# C-08_eMMC.net
KiCad netlist of a schematic drawn in Altium Designer
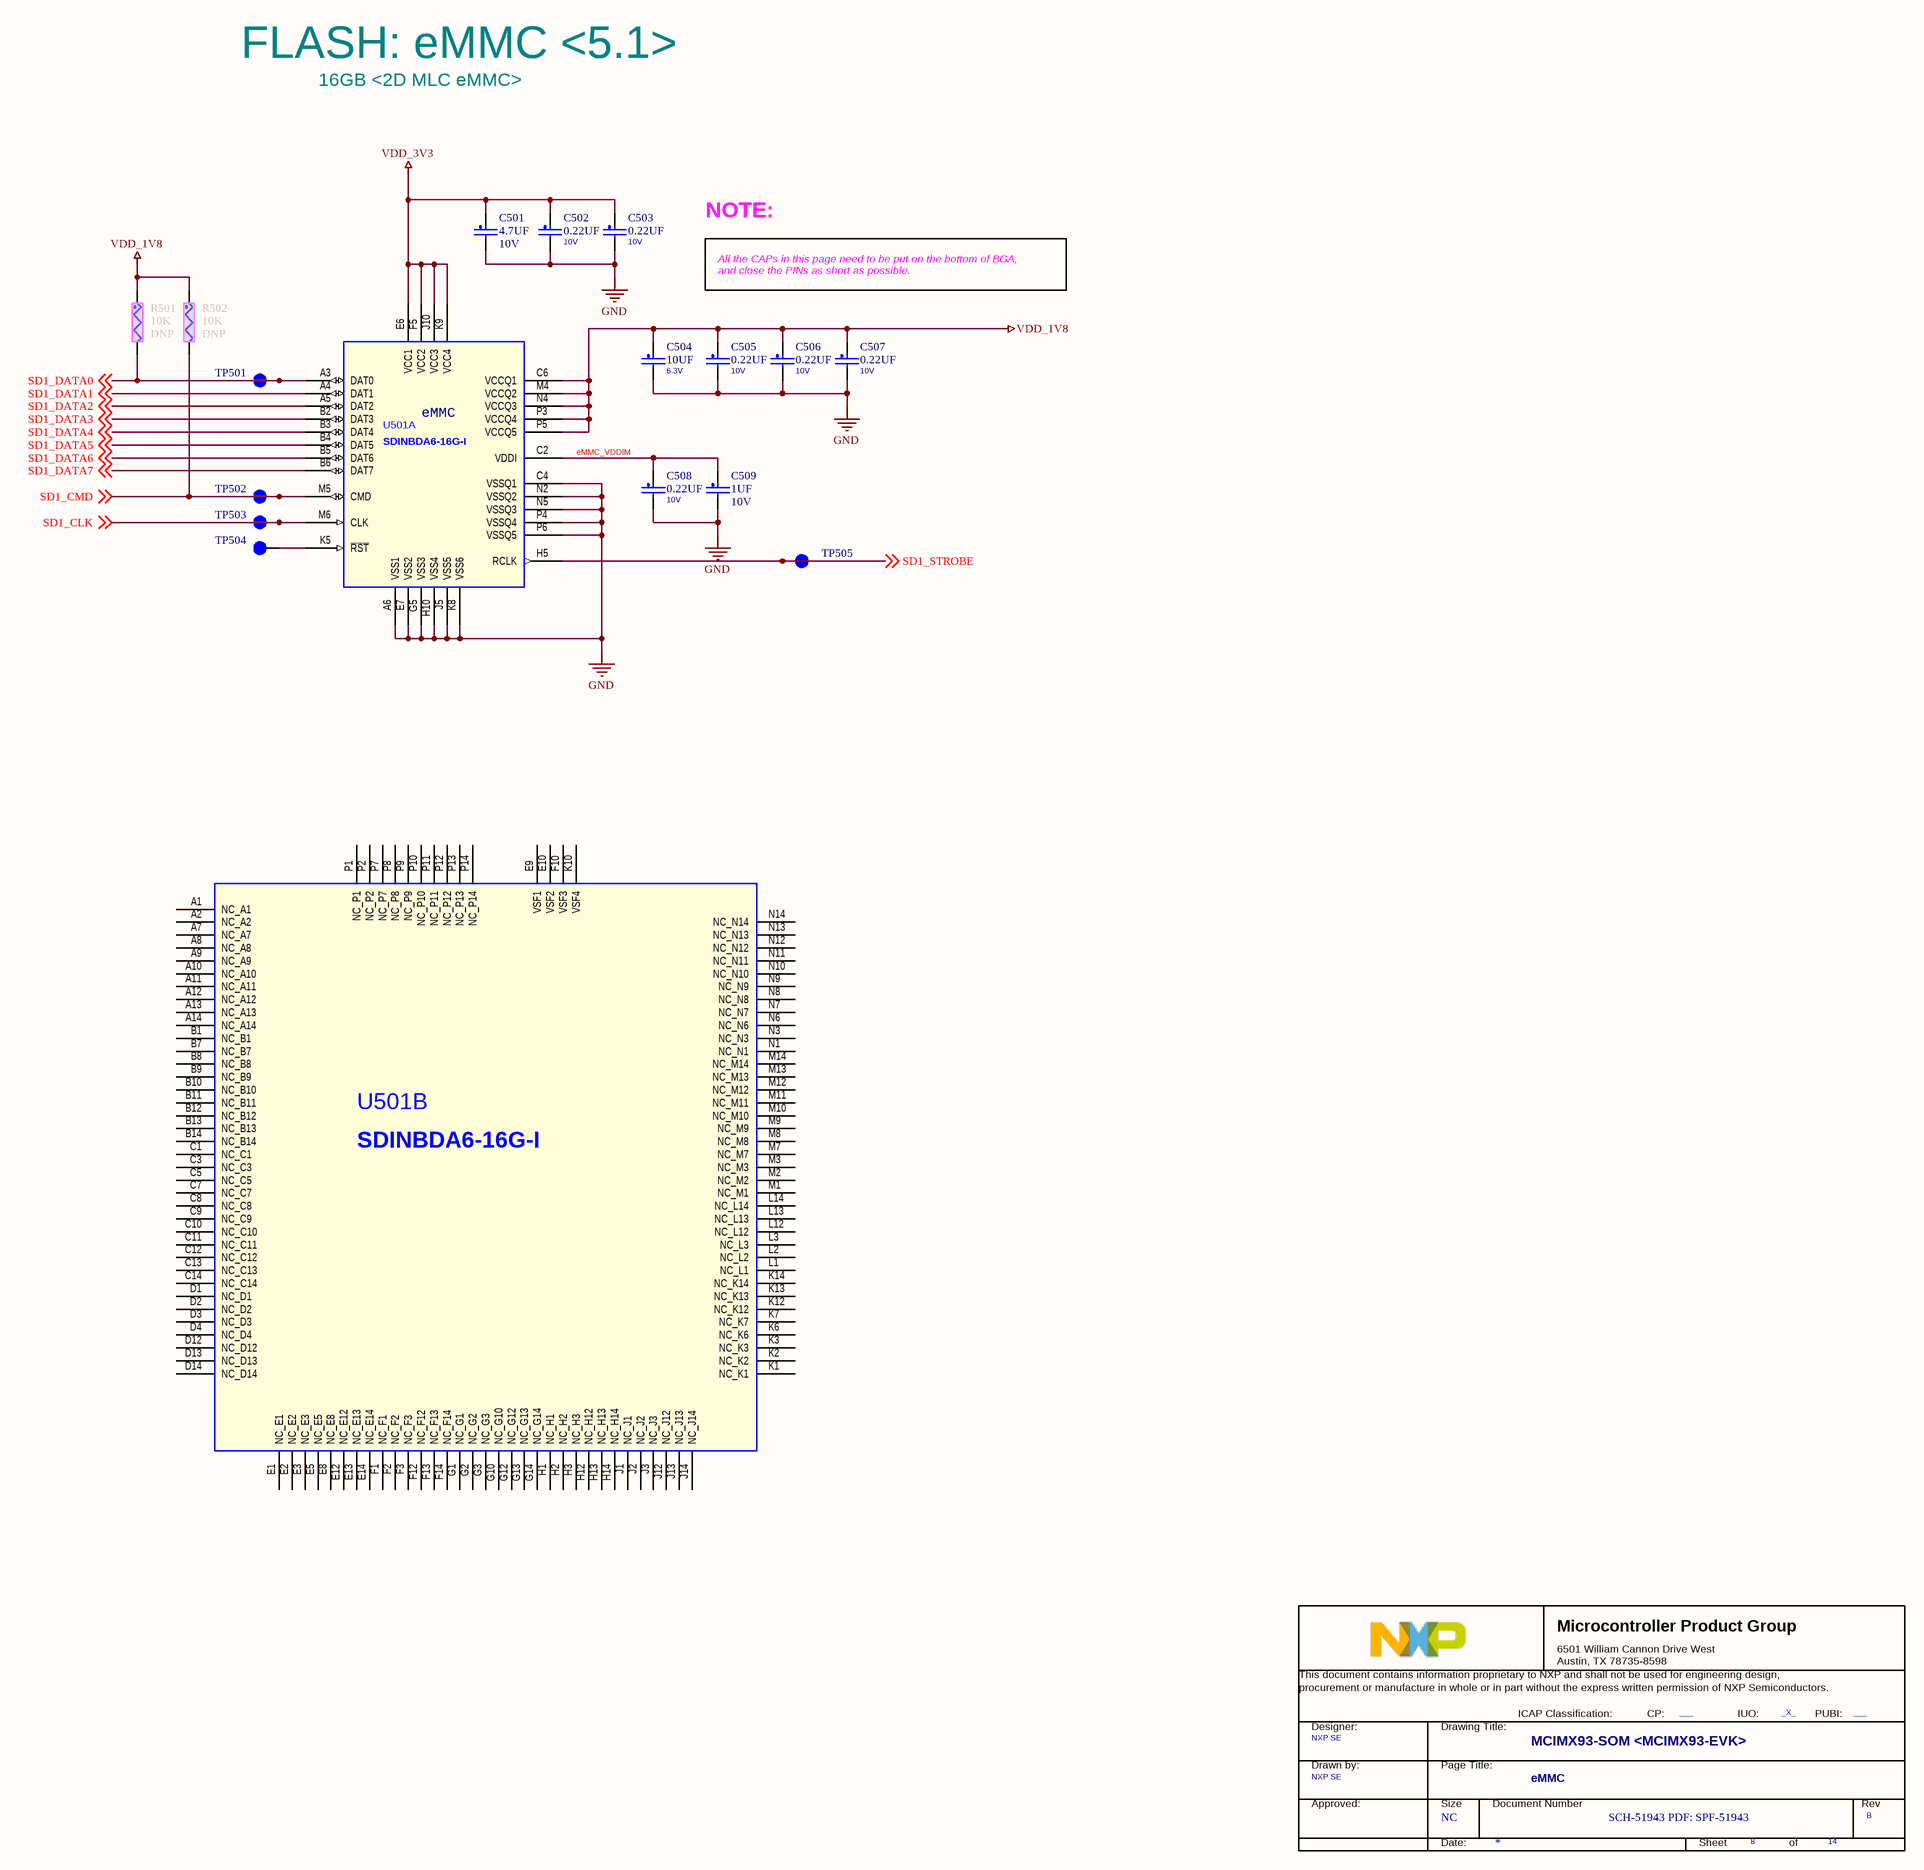
[diagram p0: C-08 eMMC.SchDoc]

(export (version "E")
  (design (tool "Eeschema 10.0.6"))
  (components
    (comp (ref "C501")
      (value "4.7UF")
      (footprint "cc0402_tol0p15")
      (description "CAP CER 4.7uF 10V 10% X5R 0402")
      (fields (field (name "TOLERANCE") "10%") (field (name "VOLTAGE") "10V"))
      (libsource (lib "*") (part "CAP_NP"))
    )
    (comp (ref "C502")
      (value "0.22UF")
      (footprint "0201_CC")
      (description "CAP CER 0.22UF 10V 20% X5R 0201")
      (fields (field (name "TOLERANCE") "20%") (field (name "VOLTAGE") "10V"))
      (libsource (lib "*") (part "CAP_NP"))
    )
    (comp (ref "C503")
      (value "0.22UF")
      (footprint "0201_CC")
      (description "CAP CER 0.22UF 10V 20% X5R 0201")
      (fields (field (name "VOLTAGE") "10V") (field (name "TOLERANCE") "20%"))
      (libsource (lib "*") (part "CAP_NP"))
    )
    (comp (ref "C504")
      (value "10UF")
      (footprint "0402_CC")
      (description "CAP CER 10UF 6.3V 20% X5R 0402")
      (fields (field (name "VOLTAGE") "6.3V") (field (name "TOLERANCE") "20%"))
      (libsource (lib "*") (part "CAP_NP"))
    )
    (comp (ref "C505")
      (value "0.22UF")
      (footprint "0201_CC")
      (description "CAP CER 0.22UF 10V 20% X5R 0201")
      (fields (field (name "VOLTAGE") "10V") (field (name "TOLERANCE") "20%"))
      (libsource (lib "*") (part "CAP_NP"))
    )
    (comp (ref "C506")
      (value "0.22UF")
      (footprint "0201_CC")
      (description "CAP CER 0.22UF 10V 20% X5R 0201")
      (fields (field (name "VOLTAGE") "10V") (field (name "TOLERANCE") "20%"))
      (libsource (lib "*") (part "CAP_NP"))
    )
    (comp (ref "C507")
      (value "0.22UF")
      (footprint "0201_CC")
      (description "CAP CER 0.22UF 10V 20% X5R 0201")
      (fields (field (name "TOLERANCE") "20%") (field (name "VOLTAGE") "10V"))
      (libsource (lib "*") (part "CAP_NP"))
    )
    (comp (ref "C508")
      (value "0.22UF")
      (footprint "0201_CC")
      (description "CAP CER 0.22UF 10V 20% X5R 0201")
      (fields (field (name "TOLERANCE") "20%") (field (name "VOLTAGE") "10V"))
      (libsource (lib "*") (part "CAP_NP"))
    )
    (comp (ref "C509")
      (value "1UF")
      (footprint "0201_CC")
      (description "CAP CER 1.0uF 10V 10% X5R 0201")
      (fields (field (name "TOLERANCE") "10%") (field (name "VOLTAGE") "10V"))
      (libsource (lib "*") (part "CAP_NP"))
    )
    (comp (ref "R501")
      (value "10K")
      (footprint "0402_CC")
      (description "RES MF 10K 1/16W 5% 0402")
      (fields (field (name "ASSY_OPT") "DNP") (field (name "TOLERANCE") "5%"))
      (libsource (lib "*") (part "RES"))
    )
    (comp (ref "R502")
      (value "10K")
      (footprint "0402_CC")
      (description "RES MF 10K 1/16W 5% 0402")
      (fields (field (name "ASSY_OPT") "DNP") (field (name "TOLERANCE") "5%"))
      (libsource (lib "*") (part "RES"))
    )
    (comp (ref "TP501")
      (value "tpad_020")
      (footprint "tpad_020")
      (description "TEST POINT PAD 0.5MM DIA SMT, NO PART TO ORDER")
      (libsource (lib "*") (part "TESTLOOP"))
    )
    (comp (ref "TP502")
      (value "tpad_020")
      (footprint "tpad_020")
      (description "TEST POINT PAD 0.5MM DIA SMT, NO PART TO ORDER")
      (libsource (lib "*") (part "TESTLOOP"))
    )
    (comp (ref "TP503")
      (value "tpad_020")
      (footprint "tpad_020")
      (description "TEST POINT PAD 0.5MM DIA SMT, NO PART TO ORDER")
      (libsource (lib "*") (part "TESTLOOP"))
    )
    (comp (ref "TP504")
      (value "TPAD_015")
      (footprint "TPAD_015")
      (description "TEST POINT PAD 15MIL DIA SMT, NO PART TO ORDER")
      (libsource (lib "*") (part "TESTLOOP"))
    )
    (comp (ref "TP505")
      (value "tpad_020")
      (footprint "tpad_020")
      (description "TEST POINT PAD 0.5MM DIA SMT, NO PART TO ORDER")
      (libsource (lib "*") (part "TESTLOOP"))
    )
    (comp (ref "U501")
      (value "SDINBDA6-16G-I")
      (footprint "fbga153_0p5_11p5x13")
      (description "IC MEM NAND FLASH 16GB MMC 5.1 CTLR 2.7-3.6V FBGA153")
      (libsource (lib "*") (part "SDINBDA6_32G_I_VFBGA_153P"))
    )
  )
  (nets
    (net (code "1") (name "/eMMC_VDDIM") (class "Default")
      (node (ref "C508") (pin "1") (pinfunction "1_1") (pintype "passive"))
      (node (ref "C509") (pin "1") (pinfunction "1_1") (pintype "passive"))
      (node (ref "U501") (pin "C2") (pinfunction "VDDI_C2") (pintype "power_in"))
    )
    (net (code "2") (name "GND") (class "Default")
      (node (ref "C501") (pin "2") (pinfunction "2_2") (pintype "passive"))
      (node (ref "C502") (pin "2") (pinfunction "2_2") (pintype "passive"))
      (node (ref "C503") (pin "2") (pinfunction "2_2") (pintype "passive"))
      (node (ref "C504") (pin "2") (pinfunction "2_2") (pintype "passive"))
      (node (ref "C505") (pin "2") (pinfunction "2_2") (pintype "passive"))
      (node (ref "C506") (pin "2") (pinfunction "2_2") (pintype "passive"))
      (node (ref "C507") (pin "2") (pinfunction "2_2") (pintype "passive"))
      (node (ref "C508") (pin "2") (pinfunction "2_2") (pintype "passive"))
      (node (ref "C509") (pin "2") (pinfunction "2_2") (pintype "passive"))
      (node (ref "U501") (pin "A6") (pinfunction "VSS1_A6") (pintype "power_in"))
      (node (ref "U501") (pin "C4") (pinfunction "VSSQ1_C4") (pintype "power_in"))
      (node (ref "U501") (pin "E7") (pinfunction "VSS2_E7") (pintype "power_in"))
      (node (ref "U501") (pin "G5") (pinfunction "VSS3_G5") (pintype "power_in"))
      (node (ref "U501") (pin "H10") (pinfunction "VSS4_H10") (pintype "power_in"))
      (node (ref "U501") (pin "J5") (pinfunction "VSS5_J5") (pintype "power_in"))
      (node (ref "U501") (pin "K8") (pinfunction "VSS6_K8") (pintype "power_in"))
      (node (ref "U501") (pin "N2") (pinfunction "VSSQ2_N2") (pintype "power_in"))
      (node (ref "U501") (pin "N5") (pinfunction "VSSQ3_N5") (pintype "power_in"))
      (node (ref "U501") (pin "P4") (pinfunction "VSSQ4_P4") (pintype "power_in"))
      (node (ref "U501") (pin "P6") (pinfunction "VSSQ5_P6") (pintype "power_in"))
    )
    (net (code "3") (name "Net-(TP504-Pin1)") (class "Default")
      (node (ref "TP504") (pin "1") (pinfunction "Pin1_1") (pintype "passive"))
      (node (ref "U501") (pin "K5") (pinfunction "~{RST}_K5") (pintype "input"))
    )
    (net (code "4") (name "SD1_CLK") (class "Default")
      (node (ref "TP503") (pin "1") (pinfunction "Pin1_1") (pintype "passive"))
      (node (ref "U501") (pin "M6") (pinfunction "CLK_M6") (pintype "input"))
    )
    (net (code "5") (name "SD1_CMD") (class "Default")
      (node (ref "R502") (pin "2") (pinfunction "2_2") (pintype "passive"))
      (node (ref "TP502") (pin "1") (pinfunction "Pin1_1") (pintype "passive"))
      (node (ref "U501") (pin "M5") (pinfunction "CMD_M5") (pintype "bidirectional"))
    )
    (net (code "6") (name "SD1_DATA0") (class "Default")
      (node (ref "R501") (pin "2") (pinfunction "2_2") (pintype "passive"))
      (node (ref "TP501") (pin "1") (pinfunction "Pin1_1") (pintype "passive"))
      (node (ref "U501") (pin "A3") (pinfunction "DAT0_A3") (pintype "bidirectional"))
    )
    (net (code "7") (name "SD1_DATA1") (class "Default")
      (node (ref "U501") (pin "A4") (pinfunction "DAT1_A4") (pintype "bidirectional"))
    )
    (net (code "8") (name "SD1_DATA2") (class "Default")
      (node (ref "U501") (pin "A5") (pinfunction "DAT2_A5") (pintype "bidirectional"))
    )
    (net (code "9") (name "SD1_DATA3") (class "Default")
      (node (ref "U501") (pin "B2") (pinfunction "DAT3_B2") (pintype "bidirectional"))
    )
    (net (code "10") (name "SD1_DATA4") (class "Default")
      (node (ref "U501") (pin "B3") (pinfunction "DAT4_B3") (pintype "bidirectional"))
    )
    (net (code "11") (name "SD1_DATA5") (class "Default")
      (node (ref "U501") (pin "B4") (pinfunction "DAT5_B4") (pintype "bidirectional"))
    )
    (net (code "12") (name "SD1_DATA6") (class "Default")
      (node (ref "U501") (pin "B5") (pinfunction "DAT6_B5") (pintype "bidirectional"))
    )
    (net (code "13") (name "SD1_DATA7") (class "Default")
      (node (ref "U501") (pin "B6") (pinfunction "DAT7_B6") (pintype "bidirectional"))
    )
    (net (code "14") (name "SD1_STROBE") (class "Default")
      (node (ref "TP505") (pin "1") (pinfunction "Pin1_1") (pintype "passive"))
      (node (ref "U501") (pin "H5") (pinfunction "RCLK_H5") (pintype "output"))
    )
    (net (code "15") (name "VDD_1V8") (class "Default")
      (node (ref "C504") (pin "1") (pinfunction "1_1") (pintype "passive"))
      (node (ref "C505") (pin "1") (pinfunction "1_1") (pintype "passive"))
      (node (ref "C506") (pin "1") (pinfunction "1_1") (pintype "passive"))
      (node (ref "C507") (pin "1") (pinfunction "1_1") (pintype "passive"))
      (node (ref "R501") (pin "1") (pinfunction "1_1") (pintype "passive"))
      (node (ref "R502") (pin "1") (pinfunction "1_1") (pintype "passive"))
      (node (ref "U501") (pin "C6") (pinfunction "VCCQ1_C6") (pintype "power_in"))
      (node (ref "U501") (pin "M4") (pinfunction "VCCQ2_M4") (pintype "power_in"))
      (node (ref "U501") (pin "N4") (pinfunction "VCCQ3_N4") (pintype "power_in"))
      (node (ref "U501") (pin "P3") (pinfunction "VCCQ4_P3") (pintype "power_in"))
      (node (ref "U501") (pin "P5") (pinfunction "VCCQ5_P5") (pintype "power_in"))
    )
    (net (code "16") (name "VDD_3V3") (class "Default")
      (node (ref "C501") (pin "1") (pinfunction "1_1") (pintype "passive"))
      (node (ref "C502") (pin "1") (pinfunction "1_1") (pintype "passive"))
      (node (ref "C503") (pin "1") (pinfunction "1_1") (pintype "passive"))
      (node (ref "U501") (pin "E6") (pinfunction "VCC1_E6") (pintype "power_in"))
      (node (ref "U501") (pin "F5") (pinfunction "VCC2_F5") (pintype "power_in"))
      (node (ref "U501") (pin "J10") (pinfunction "VCC3_J10") (pintype "power_in"))
      (node (ref "U501") (pin "K9") (pinfunction "VCC4_K9") (pintype "power_in"))
    )
    (net (code "17") (name "unconnected-(U501B-NC_A1-PadA1)") (class "Default")
      (node (ref "U501") (pin "A1") (pinfunction "NC_A1_A1") (pintype "passive"))
    )
    (net (code "18") (name "unconnected-(U501B-NC_A2-PadA2)") (class "Default")
      (node (ref "U501") (pin "A2") (pinfunction "NC_A2_A2") (pintype "passive"))
    )
    (net (code "19") (name "unconnected-(U501B-NC_A7-PadA7)") (class "Default")
      (node (ref "U501") (pin "A7") (pinfunction "NC_A7_A7") (pintype "passive"))
    )
    (net (code "20") (name "unconnected-(U501B-NC_A8-PadA8)") (class "Default")
      (node (ref "U501") (pin "A8") (pinfunction "NC_A8_A8") (pintype "passive"))
    )
    (net (code "21") (name "unconnected-(U501B-NC_A9-PadA9)") (class "Default")
      (node (ref "U501") (pin "A9") (pinfunction "NC_A9_A9") (pintype "passive"))
    )
    (net (code "22") (name "unconnected-(U501B-NC_A10-PadA10)") (class "Default")
      (node (ref "U501") (pin "A10") (pinfunction "NC_A10_A10") (pintype "passive"))
    )
    (net (code "23") (name "unconnected-(U501B-NC_A11-PadA11)") (class "Default")
      (node (ref "U501") (pin "A11") (pinfunction "NC_A11_A11") (pintype "passive"))
    )
    (net (code "24") (name "unconnected-(U501B-NC_A12-PadA12)") (class "Default")
      (node (ref "U501") (pin "A12") (pinfunction "NC_A12_A12") (pintype "passive"))
    )
    (net (code "25") (name "unconnected-(U501B-NC_A13-PadA13)") (class "Default")
      (node (ref "U501") (pin "A13") (pinfunction "NC_A13_A13") (pintype "passive"))
    )
    (net (code "26") (name "unconnected-(U501B-NC_A14-PadA14)") (class "Default")
      (node (ref "U501") (pin "A14") (pinfunction "NC_A14_A14") (pintype "passive"))
    )
    (net (code "27") (name "unconnected-(U501B-NC_B1-PadB1)") (class "Default")
      (node (ref "U501") (pin "B1") (pinfunction "NC_B1_B1") (pintype "passive"))
    )
    (net (code "28") (name "unconnected-(U501B-NC_B7-PadB7)") (class "Default")
      (node (ref "U501") (pin "B7") (pinfunction "NC_B7_B7") (pintype "passive"))
    )
    (net (code "29") (name "unconnected-(U501B-NC_B8-PadB8)") (class "Default")
      (node (ref "U501") (pin "B8") (pinfunction "NC_B8_B8") (pintype "passive"))
    )
    (net (code "30") (name "unconnected-(U501B-NC_B9-PadB9)") (class "Default")
      (node (ref "U501") (pin "B9") (pinfunction "NC_B9_B9") (pintype "passive"))
    )
    (net (code "31") (name "unconnected-(U501B-NC_B10-PadB10)") (class "Default")
      (node (ref "U501") (pin "B10") (pinfunction "NC_B10_B10") (pintype "passive"))
    )
    (net (code "32") (name "unconnected-(U501B-NC_B11-PadB11)") (class "Default")
      (node (ref "U501") (pin "B11") (pinfunction "NC_B11_B11") (pintype "passive"))
    )
    (net (code "33") (name "unconnected-(U501B-NC_B12-PadB12)") (class "Default")
      (node (ref "U501") (pin "B12") (pinfunction "NC_B12_B12") (pintype "passive"))
    )
    (net (code "34") (name "unconnected-(U501B-NC_B13-PadB13)") (class "Default")
      (node (ref "U501") (pin "B13") (pinfunction "NC_B13_B13") (pintype "passive"))
    )
    (net (code "35") (name "unconnected-(U501B-NC_B14-PadB14)") (class "Default")
      (node (ref "U501") (pin "B14") (pinfunction "NC_B14_B14") (pintype "passive"))
    )
    (net (code "36") (name "unconnected-(U501B-NC_C1-PadC1)") (class "Default")
      (node (ref "U501") (pin "C1") (pinfunction "NC_C1_C1") (pintype "passive"))
    )
    (net (code "37") (name "unconnected-(U501B-NC_C3-PadC3)") (class "Default")
      (node (ref "U501") (pin "C3") (pinfunction "NC_C3_C3") (pintype "passive"))
    )
    (net (code "38") (name "unconnected-(U501B-NC_C5-PadC5)") (class "Default")
      (node (ref "U501") (pin "C5") (pinfunction "NC_C5_C5") (pintype "passive"))
    )
    (net (code "39") (name "unconnected-(U501B-NC_C7-PadC7)") (class "Default")
      (node (ref "U501") (pin "C7") (pinfunction "NC_C7_C7") (pintype "passive"))
    )
    (net (code "40") (name "unconnected-(U501B-NC_C8-PadC8)") (class "Default")
      (node (ref "U501") (pin "C8") (pinfunction "NC_C8_C8") (pintype "passive"))
    )
    (net (code "41") (name "unconnected-(U501B-NC_C9-PadC9)") (class "Default")
      (node (ref "U501") (pin "C9") (pinfunction "NC_C9_C9") (pintype "passive"))
    )
    (net (code "42") (name "unconnected-(U501B-NC_C10-PadC10)") (class "Default")
      (node (ref "U501") (pin "C10") (pinfunction "NC_C10_C10") (pintype "passive"))
    )
    (net (code "43") (name "unconnected-(U501B-NC_C11-PadC11)") (class "Default")
      (node (ref "U501") (pin "C11") (pinfunction "NC_C11_C11") (pintype "passive"))
    )
    (net (code "44") (name "unconnected-(U501B-NC_C12-PadC12)") (class "Default")
      (node (ref "U501") (pin "C12") (pinfunction "NC_C12_C12") (pintype "passive"))
    )
    (net (code "45") (name "unconnected-(U501B-NC_C13-PadC13)") (class "Default")
      (node (ref "U501") (pin "C13") (pinfunction "NC_C13_C13") (pintype "passive"))
    )
    (net (code "46") (name "unconnected-(U501B-NC_C14-PadC14)") (class "Default")
      (node (ref "U501") (pin "C14") (pinfunction "NC_C14_C14") (pintype "passive"))
    )
    (net (code "47") (name "unconnected-(U501B-NC_D1-PadD1)") (class "Default")
      (node (ref "U501") (pin "D1") (pinfunction "NC_D1_D1") (pintype "passive"))
    )
    (net (code "48") (name "unconnected-(U501B-NC_D2-PadD2)") (class "Default")
      (node (ref "U501") (pin "D2") (pinfunction "NC_D2_D2") (pintype "passive"))
    )
    (net (code "49") (name "unconnected-(U501B-NC_D3-PadD3)") (class "Default")
      (node (ref "U501") (pin "D3") (pinfunction "NC_D3_D3") (pintype "passive"))
    )
    (net (code "50") (name "unconnected-(U501B-NC_D4-PadD4)") (class "Default")
      (node (ref "U501") (pin "D4") (pinfunction "NC_D4_D4") (pintype "passive"))
    )
    (net (code "51") (name "unconnected-(U501B-NC_D12-PadD12)") (class "Default")
      (node (ref "U501") (pin "D12") (pinfunction "NC_D12_D12") (pintype "passive"))
    )
    (net (code "52") (name "unconnected-(U501B-NC_D13-PadD13)") (class "Default")
      (node (ref "U501") (pin "D13") (pinfunction "NC_D13_D13") (pintype "passive"))
    )
    (net (code "53") (name "unconnected-(U501B-NC_D14-PadD14)") (class "Default")
      (node (ref "U501") (pin "D14") (pinfunction "NC_D14_D14") (pintype "passive"))
    )
    (net (code "54") (name "unconnected-(U501B-NC_E1-PadE1)") (class "Default")
      (node (ref "U501") (pin "E1") (pinfunction "NC_E1_E1") (pintype "passive"))
    )
    (net (code "55") (name "unconnected-(U501B-NC_E2-PadE2)") (class "Default")
      (node (ref "U501") (pin "E2") (pinfunction "NC_E2_E2") (pintype "passive"))
    )
    (net (code "56") (name "unconnected-(U501B-NC_E3-PadE3)") (class "Default")
      (node (ref "U501") (pin "E3") (pinfunction "NC_E3_E3") (pintype "passive"))
    )
    (net (code "57") (name "unconnected-(U501B-NC_E5-PadE5)") (class "Default")
      (node (ref "U501") (pin "E5") (pinfunction "NC_E5_E5") (pintype "passive"))
    )
    (net (code "58") (name "unconnected-(U501B-NC_E8-PadE8)") (class "Default")
      (node (ref "U501") (pin "E8") (pinfunction "NC_E8_E8") (pintype "passive"))
    )
    (net (code "59") (name "unconnected-(U501B-NC_E12-PadE12)") (class "Default")
      (node (ref "U501") (pin "E12") (pinfunction "NC_E12_E12") (pintype "passive"))
    )
    (net (code "60") (name "unconnected-(U501B-NC_E13-PadE13)") (class "Default")
      (node (ref "U501") (pin "E13") (pinfunction "NC_E13_E13") (pintype "passive"))
    )
    (net (code "61") (name "unconnected-(U501B-NC_E14-PadE14)") (class "Default")
      (node (ref "U501") (pin "E14") (pinfunction "NC_E14_E14") (pintype "passive"))
    )
    (net (code "62") (name "unconnected-(U501B-NC_F1-PadF1)") (class "Default")
      (node (ref "U501") (pin "F1") (pinfunction "NC_F1_F1") (pintype "passive"))
    )
    (net (code "63") (name "unconnected-(U501B-NC_F2-PadF2)") (class "Default")
      (node (ref "U501") (pin "F2") (pinfunction "NC_F2_F2") (pintype "passive"))
    )
    (net (code "64") (name "unconnected-(U501B-NC_F3-PadF3)") (class "Default")
      (node (ref "U501") (pin "F3") (pinfunction "NC_F3_F3") (pintype "passive"))
    )
    (net (code "65") (name "unconnected-(U501B-NC_F12-PadF12)") (class "Default")
      (node (ref "U501") (pin "F12") (pinfunction "NC_F12_F12") (pintype "passive"))
    )
    (net (code "66") (name "unconnected-(U501B-NC_F13-PadF13)") (class "Default")
      (node (ref "U501") (pin "F13") (pinfunction "NC_F13_F13") (pintype "passive"))
    )
    (net (code "67") (name "unconnected-(U501B-NC_F14-PadF14)") (class "Default")
      (node (ref "U501") (pin "F14") (pinfunction "NC_F14_F14") (pintype "passive"))
    )
    (net (code "68") (name "unconnected-(U501B-NC_G1-PadG1)") (class "Default")
      (node (ref "U501") (pin "G1") (pinfunction "NC_G1_G1") (pintype "passive"))
    )
    (net (code "69") (name "unconnected-(U501B-NC_G2-PadG2)") (class "Default")
      (node (ref "U501") (pin "G2") (pinfunction "NC_G2_G2") (pintype "passive"))
    )
    (net (code "70") (name "unconnected-(U501B-NC_G3-PadG3)") (class "Default")
      (node (ref "U501") (pin "G3") (pinfunction "NC_G3_G3") (pintype "passive"))
    )
    (net (code "71") (name "unconnected-(U501B-NC_G10-PadG10)") (class "Default")
      (node (ref "U501") (pin "G10") (pinfunction "NC_G10_G10") (pintype "passive"))
    )
    (net (code "72") (name "unconnected-(U501B-NC_G12-PadG12)") (class "Default")
      (node (ref "U501") (pin "G12") (pinfunction "NC_G12_G12") (pintype "passive"))
    )
    (net (code "73") (name "unconnected-(U501B-NC_G13-PadG13)") (class "Default")
      (node (ref "U501") (pin "G13") (pinfunction "NC_G13_G13") (pintype "passive"))
    )
    (net (code "74") (name "unconnected-(U501B-NC_G14-PadG14)") (class "Default")
      (node (ref "U501") (pin "G14") (pinfunction "NC_G14_G14") (pintype "passive"))
    )
    (net (code "75") (name "unconnected-(U501B-NC_H1-PadH1)") (class "Default")
      (node (ref "U501") (pin "H1") (pinfunction "NC_H1_H1") (pintype "passive"))
    )
    (net (code "76") (name "unconnected-(U501B-NC_H2-PadH2)") (class "Default")
      (node (ref "U501") (pin "H2") (pinfunction "NC_H2_H2") (pintype "passive"))
    )
    (net (code "77") (name "unconnected-(U501B-NC_H3-PadH3)") (class "Default")
      (node (ref "U501") (pin "H3") (pinfunction "NC_H3_H3") (pintype "passive"))
    )
    (net (code "78") (name "unconnected-(U501B-NC_H12-PadH12)") (class "Default")
      (node (ref "U501") (pin "H12") (pinfunction "NC_H12_H12") (pintype "passive"))
    )
    (net (code "79") (name "unconnected-(U501B-NC_H13-PadH13)") (class "Default")
      (node (ref "U501") (pin "H13") (pinfunction "NC_H13_H13") (pintype "passive"))
    )
    (net (code "80") (name "unconnected-(U501B-NC_H14-PadH14)") (class "Default")
      (node (ref "U501") (pin "H14") (pinfunction "NC_H14_H14") (pintype "passive"))
    )
    (net (code "81") (name "unconnected-(U501B-NC_J1-PadJ1)") (class "Default")
      (node (ref "U501") (pin "J1") (pinfunction "NC_J1_J1") (pintype "passive"))
    )
    (net (code "82") (name "unconnected-(U501B-NC_J2-PadJ2)") (class "Default")
      (node (ref "U501") (pin "J2") (pinfunction "NC_J2_J2") (pintype "passive"))
    )
    (net (code "83") (name "unconnected-(U501B-NC_J3-PadJ3)") (class "Default")
      (node (ref "U501") (pin "J3") (pinfunction "NC_J3_J3") (pintype "passive"))
    )
    (net (code "84") (name "unconnected-(U501B-NC_J12-PadJ12)") (class "Default")
      (node (ref "U501") (pin "J12") (pinfunction "NC_J12_J12") (pintype "passive"))
    )
    (net (code "85") (name "unconnected-(U501B-NC_J13-PadJ13)") (class "Default")
      (node (ref "U501") (pin "J13") (pinfunction "NC_J13_J13") (pintype "passive"))
    )
    (net (code "86") (name "unconnected-(U501B-NC_J14-PadJ14)") (class "Default")
      (node (ref "U501") (pin "J14") (pinfunction "NC_J14_J14") (pintype "passive"))
    )
    (net (code "87") (name "unconnected-(U501B-NC_K1-PadK1)") (class "Default")
      (node (ref "U501") (pin "K1") (pinfunction "NC_K1_K1") (pintype "passive"))
    )
    (net (code "88") (name "unconnected-(U501B-NC_K2-PadK2)") (class "Default")
      (node (ref "U501") (pin "K2") (pinfunction "NC_K2_K2") (pintype "passive"))
    )
    (net (code "89") (name "unconnected-(U501B-NC_K3-PadK3)") (class "Default")
      (node (ref "U501") (pin "K3") (pinfunction "NC_K3_K3") (pintype "passive"))
    )
    (net (code "90") (name "unconnected-(U501B-NC_K6-PadK6)") (class "Default")
      (node (ref "U501") (pin "K6") (pinfunction "NC_K6_K6") (pintype "passive"))
    )
    (net (code "91") (name "unconnected-(U501B-NC_K7-PadK7)") (class "Default")
      (node (ref "U501") (pin "K7") (pinfunction "NC_K7_K7") (pintype "passive"))
    )
    (net (code "92") (name "unconnected-(U501B-NC_K12-PadK12)") (class "Default")
      (node (ref "U501") (pin "K12") (pinfunction "NC_K12_K12") (pintype "passive"))
    )
    (net (code "93") (name "unconnected-(U501B-NC_K13-PadK13)") (class "Default")
      (node (ref "U501") (pin "K13") (pinfunction "NC_K13_K13") (pintype "passive"))
    )
    (net (code "94") (name "unconnected-(U501B-NC_K14-PadK14)") (class "Default")
      (node (ref "U501") (pin "K14") (pinfunction "NC_K14_K14") (pintype "passive"))
    )
    (net (code "95") (name "unconnected-(U501B-NC_L1-PadL1)") (class "Default")
      (node (ref "U501") (pin "L1") (pinfunction "NC_L1_L1") (pintype "passive"))
    )
    (net (code "96") (name "unconnected-(U501B-NC_L2-PadL2)") (class "Default")
      (node (ref "U501") (pin "L2") (pinfunction "NC_L2_L2") (pintype "passive"))
    )
    (net (code "97") (name "unconnected-(U501B-NC_L3-PadL3)") (class "Default")
      (node (ref "U501") (pin "L3") (pinfunction "NC_L3_L3") (pintype "passive"))
    )
    (net (code "98") (name "unconnected-(U501B-NC_L12-PadL12)") (class "Default")
      (node (ref "U501") (pin "L12") (pinfunction "NC_L12_L12") (pintype "passive"))
    )
    (net (code "99") (name "unconnected-(U501B-NC_L13-PadL13)") (class "Default")
      (node (ref "U501") (pin "L13") (pinfunction "NC_L13_L13") (pintype "passive"))
    )
    (net (code "100") (name "unconnected-(U501B-NC_L14-PadL14)") (class "Default")
      (node (ref "U501") (pin "L14") (pinfunction "NC_L14_L14") (pintype "passive"))
    )
    (net (code "101") (name "unconnected-(U501B-NC_M1-PadM1)") (class "Default")
      (node (ref "U501") (pin "M1") (pinfunction "NC_M1_M1") (pintype "passive"))
    )
    (net (code "102") (name "unconnected-(U501B-NC_M2-PadM2)") (class "Default")
      (node (ref "U501") (pin "M2") (pinfunction "NC_M2_M2") (pintype "passive"))
    )
    (net (code "103") (name "unconnected-(U501B-NC_M3-PadM3)") (class "Default")
      (node (ref "U501") (pin "M3") (pinfunction "NC_M3_M3") (pintype "passive"))
    )
    (net (code "104") (name "unconnected-(U501B-NC_M7-PadM7)") (class "Default")
      (node (ref "U501") (pin "M7") (pinfunction "NC_M7_M7") (pintype "passive"))
    )
    (net (code "105") (name "unconnected-(U501B-NC_M8-PadM8)") (class "Default")
      (node (ref "U501") (pin "M8") (pinfunction "NC_M8_M8") (pintype "passive"))
    )
    (net (code "106") (name "unconnected-(U501B-NC_M9-PadM9)") (class "Default")
      (node (ref "U501") (pin "M9") (pinfunction "NC_M9_M9") (pintype "passive"))
    )
    (net (code "107") (name "unconnected-(U501B-NC_M10-PadM10)") (class "Default")
      (node (ref "U501") (pin "M10") (pinfunction "NC_M10_M10") (pintype "passive"))
    )
    (net (code "108") (name "unconnected-(U501B-NC_M11-PadM11)") (class "Default")
      (node (ref "U501") (pin "M11") (pinfunction "NC_M11_M11") (pintype "passive"))
    )
    (net (code "109") (name "unconnected-(U501B-NC_M12-PadM12)") (class "Default")
      (node (ref "U501") (pin "M12") (pinfunction "NC_M12_M12") (pintype "passive"))
    )
    (net (code "110") (name "unconnected-(U501B-NC_M13-PadM13)") (class "Default")
      (node (ref "U501") (pin "M13") (pinfunction "NC_M13_M13") (pintype "passive"))
    )
    (net (code "111") (name "unconnected-(U501B-NC_M14-PadM14)") (class "Default")
      (node (ref "U501") (pin "M14") (pinfunction "NC_M14_M14") (pintype "passive"))
    )
    (net (code "112") (name "unconnected-(U501B-NC_N1-PadN1)") (class "Default")
      (node (ref "U501") (pin "N1") (pinfunction "NC_N1_N1") (pintype "passive"))
    )
    (net (code "113") (name "unconnected-(U501B-NC_N3-PadN3)") (class "Default")
      (node (ref "U501") (pin "N3") (pinfunction "NC_N3_N3") (pintype "passive"))
    )
    (net (code "114") (name "unconnected-(U501B-NC_N6-PadN6)") (class "Default")
      (node (ref "U501") (pin "N6") (pinfunction "NC_N6_N6") (pintype "passive"))
    )
    (net (code "115") (name "unconnected-(U501B-NC_N7-PadN7)") (class "Default")
      (node (ref "U501") (pin "N7") (pinfunction "NC_N7_N7") (pintype "passive"))
    )
    (net (code "116") (name "unconnected-(U501B-NC_N8-PadN8)") (class "Default")
      (node (ref "U501") (pin "N8") (pinfunction "NC_N8_N8") (pintype "passive"))
    )
    (net (code "117") (name "unconnected-(U501B-NC_N9-PadN9)") (class "Default")
      (node (ref "U501") (pin "N9") (pinfunction "NC_N9_N9") (pintype "passive"))
    )
    (net (code "118") (name "unconnected-(U501B-NC_N10-PadN10)") (class "Default")
      (node (ref "U501") (pin "N10") (pinfunction "NC_N10_N10") (pintype "passive"))
    )
    (net (code "119") (name "unconnected-(U501B-NC_N11-PadN11)") (class "Default")
      (node (ref "U501") (pin "N11") (pinfunction "NC_N11_N11") (pintype "passive"))
    )
    (net (code "120") (name "unconnected-(U501B-NC_N12-PadN12)") (class "Default")
      (node (ref "U501") (pin "N12") (pinfunction "NC_N12_N12") (pintype "passive"))
    )
    (net (code "121") (name "unconnected-(U501B-NC_N13-PadN13)") (class "Default")
      (node (ref "U501") (pin "N13") (pinfunction "NC_N13_N13") (pintype "passive"))
    )
    (net (code "122") (name "unconnected-(U501B-NC_N14-PadN14)") (class "Default")
      (node (ref "U501") (pin "N14") (pinfunction "NC_N14_N14") (pintype "passive"))
    )
    (net (code "123") (name "unconnected-(U501B-NC_P1-PadP1)") (class "Default")
      (node (ref "U501") (pin "P1") (pinfunction "NC_P1_P1") (pintype "passive"))
    )
    (net (code "124") (name "unconnected-(U501B-NC_P2-PadP2)") (class "Default")
      (node (ref "U501") (pin "P2") (pinfunction "NC_P2_P2") (pintype "passive"))
    )
    (net (code "125") (name "unconnected-(U501B-NC_P7-PadP7)") (class "Default")
      (node (ref "U501") (pin "P7") (pinfunction "NC_P7_P7") (pintype "passive"))
    )
    (net (code "126") (name "unconnected-(U501B-NC_P8-PadP8)") (class "Default")
      (node (ref "U501") (pin "P8") (pinfunction "NC_P8_P8") (pintype "passive"))
    )
    (net (code "127") (name "unconnected-(U501B-NC_P9-PadP9)") (class "Default")
      (node (ref "U501") (pin "P9") (pinfunction "NC_P9_P9") (pintype "passive"))
    )
    (net (code "128") (name "unconnected-(U501B-NC_P10-PadP10)") (class "Default")
      (node (ref "U501") (pin "P10") (pinfunction "NC_P10_P10") (pintype "passive"))
    )
    (net (code "129") (name "unconnected-(U501B-NC_P11-PadP11)") (class "Default")
      (node (ref "U501") (pin "P11") (pinfunction "NC_P11_P11") (pintype "passive"))
    )
    (net (code "130") (name "unconnected-(U501B-NC_P12-PadP12)") (class "Default")
      (node (ref "U501") (pin "P12") (pinfunction "NC_P12_P12") (pintype "passive"))
    )
    (net (code "131") (name "unconnected-(U501B-NC_P13-PadP13)") (class "Default")
      (node (ref "U501") (pin "P13") (pinfunction "NC_P13_P13") (pintype "passive"))
    )
    (net (code "132") (name "unconnected-(U501B-NC_P14-PadP14)") (class "Default")
      (node (ref "U501") (pin "P14") (pinfunction "NC_P14_P14") (pintype "passive"))
    )
    (net (code "133") (name "unconnected-(U501B-VSF1-PadE9)") (class "Default")
      (node (ref "U501") (pin "E9") (pinfunction "VSF1_E9") (pintype "passive"))
    )
    (net (code "134") (name "unconnected-(U501B-VSF2-PadE10)") (class "Default")
      (node (ref "U501") (pin "E10") (pinfunction "VSF2_E10") (pintype "passive"))
    )
    (net (code "135") (name "unconnected-(U501B-VSF3-PadF10)") (class "Default")
      (node (ref "U501") (pin "F10") (pinfunction "VSF3_F10") (pintype "passive"))
    )
    (net (code "136") (name "unconnected-(U501B-VSF4-PadK10)") (class "Default")
      (node (ref "U501") (pin "K10") (pinfunction "VSF4_K10") (pintype "passive"))
    )
  )
)
